# BREADBOARD_MATTRIX.net
KiCad netlist of a schematic drawn in Altium Designer
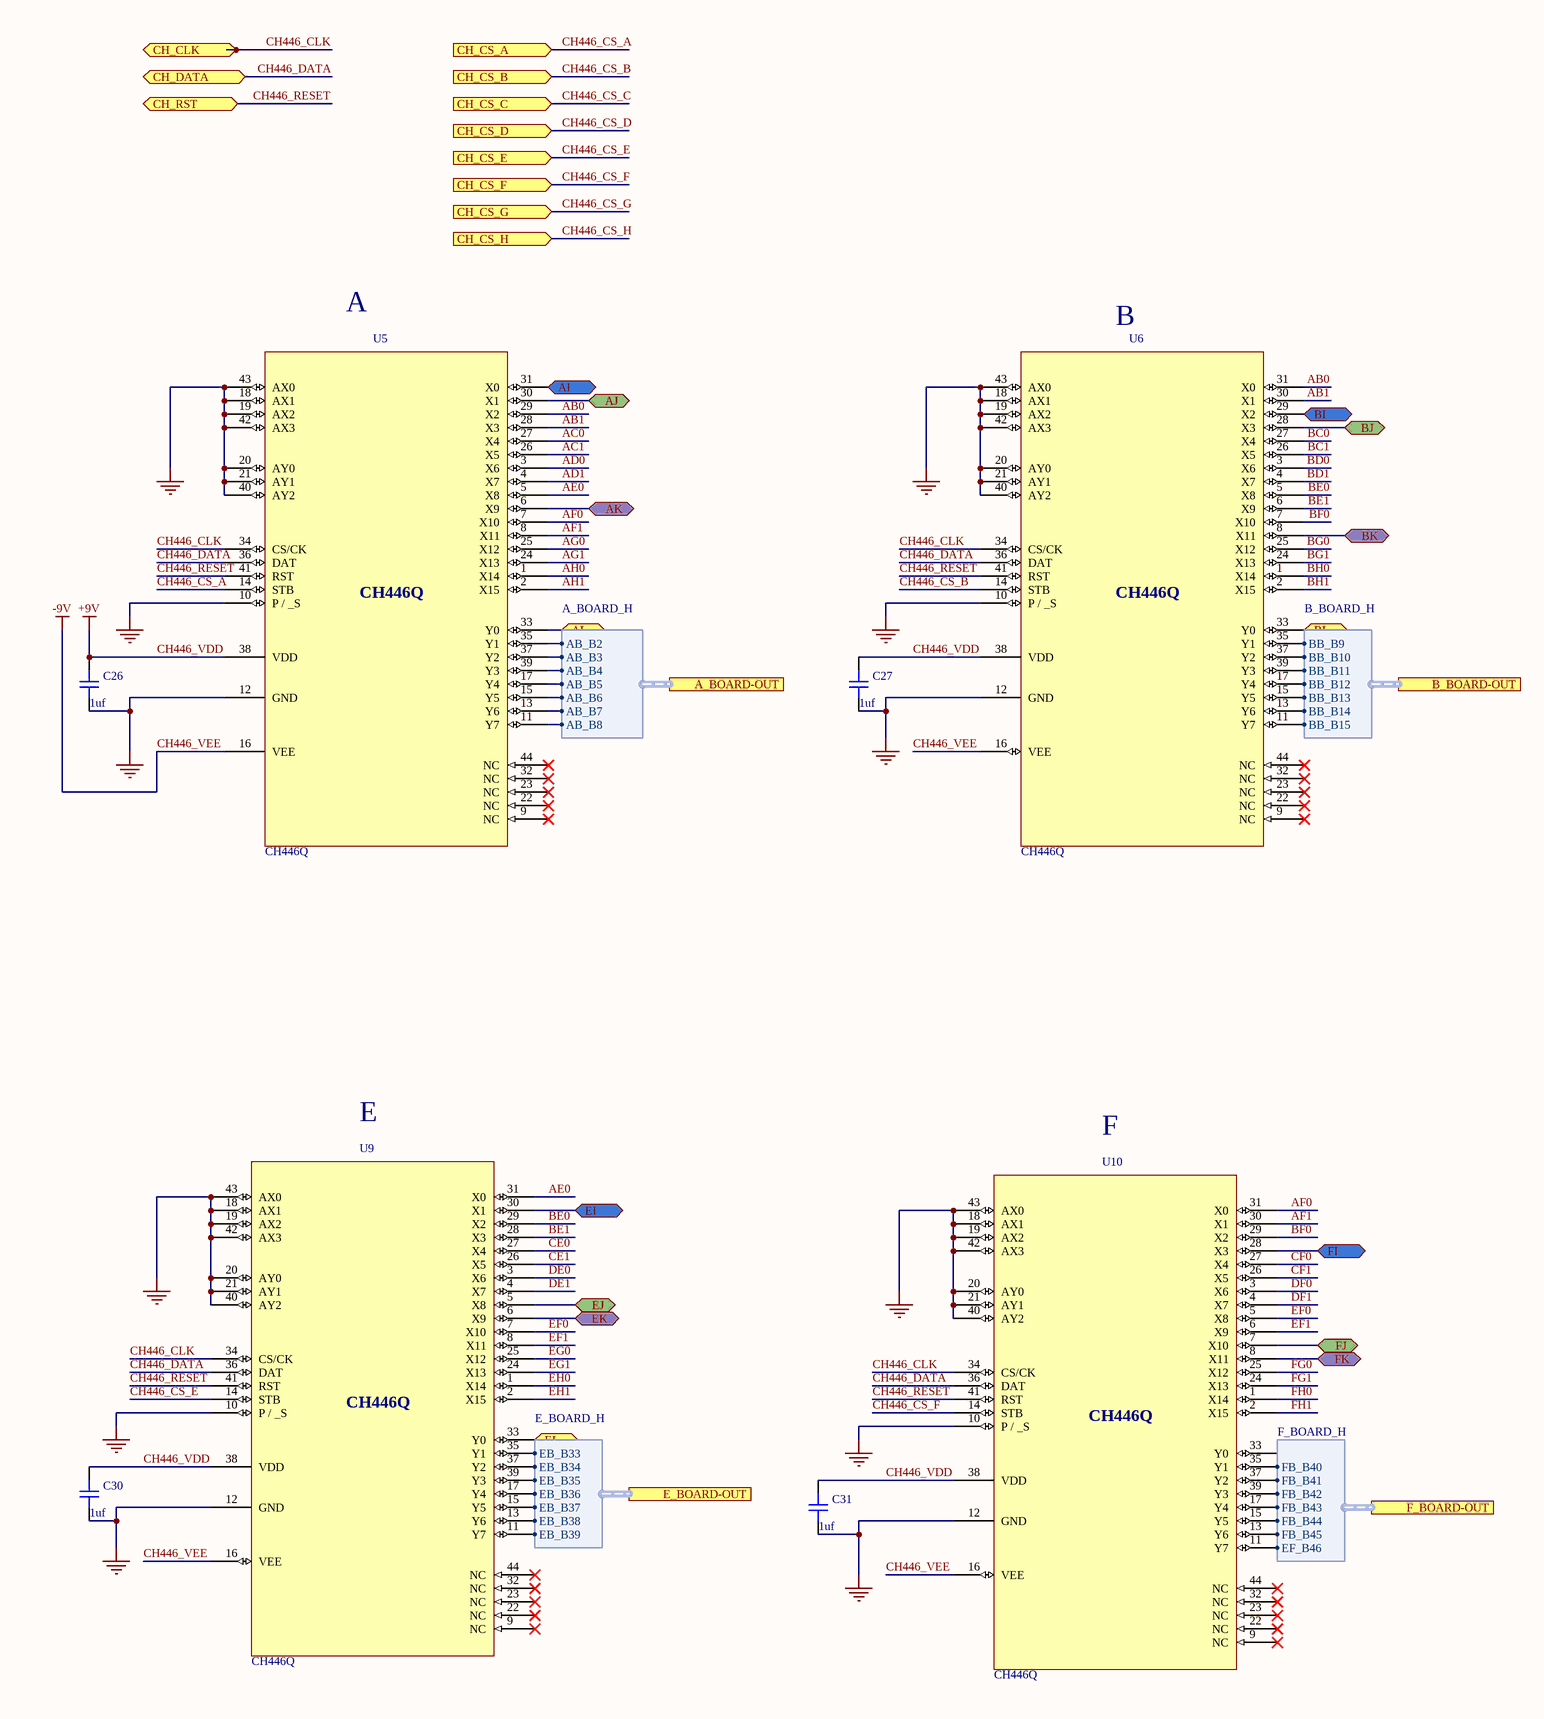
[diagram p0: BREADBOARD_MATTRIX.SchDoc, left]
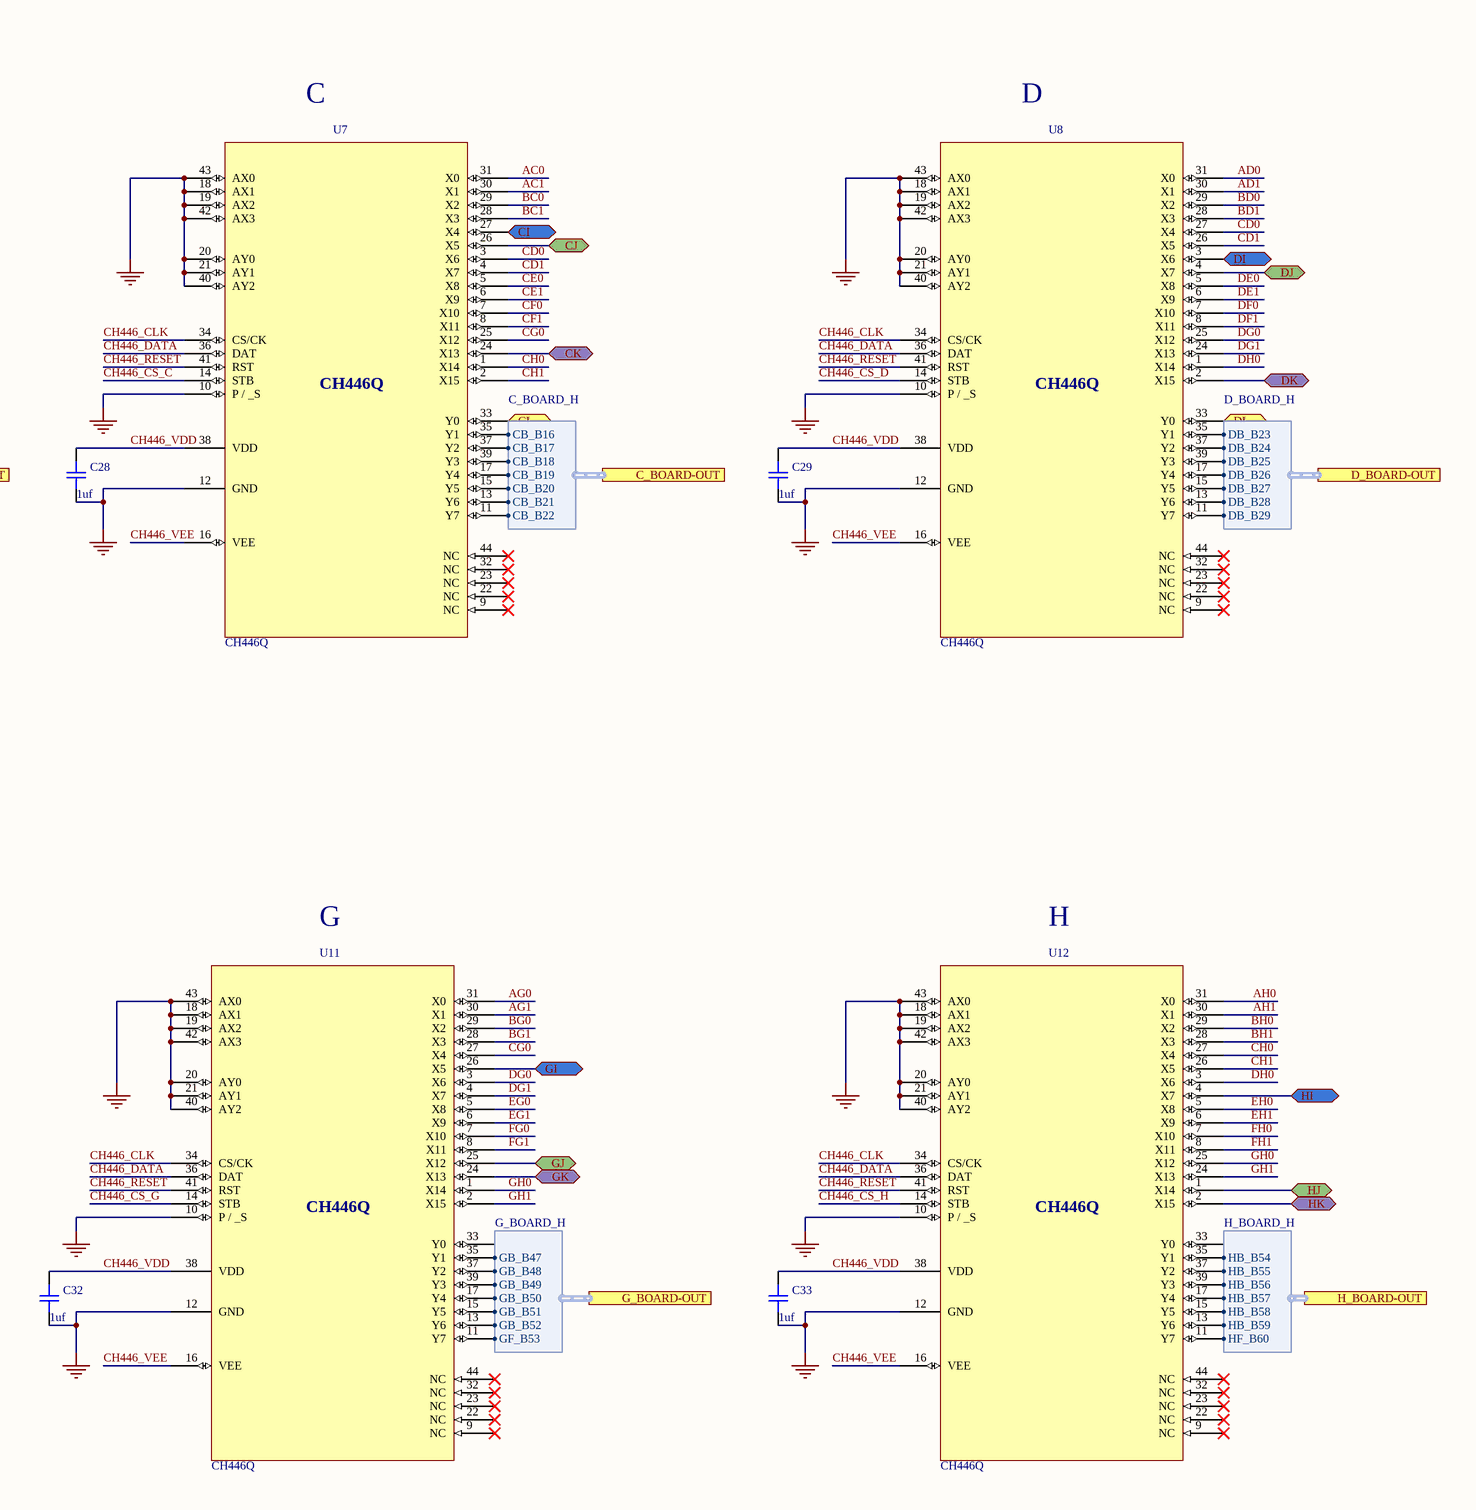
[diagram p1: BREADBOARD_MATTRIX.SchDoc, right]

(export (version "E")
  (design (tool "Eeschema 10.0.6"))
  (components
    (comp (ref "C26")
      (value "1uf")
      (footprint "CAP_0603")
      (description "Capacitor SMD 0603")
      (libsource (lib "Schematic-Lib-PhilsLab") (part "CAP_0603"))
    )
    (comp (ref "C27")
      (value "1uf")
      (footprint "CAP_0603")
      (description "Capacitor SMD 0603")
      (libsource (lib "Schematic-Lib-PhilsLab") (part "CAP_0603"))
    )
    (comp (ref "C28")
      (value "1uf")
      (footprint "CAP_0603")
      (description "Capacitor SMD 0603")
      (libsource (lib "Schematic-Lib-PhilsLab") (part "CAP_0603"))
    )
    (comp (ref "C29")
      (value "1uf")
      (footprint "CAP_0603")
      (description "Capacitor SMD 0603")
      (libsource (lib "Schematic-Lib-PhilsLab") (part "CAP_0603"))
    )
    (comp (ref "C30")
      (value "1uf")
      (footprint "CAP_0603")
      (description "Capacitor SMD 0603")
      (libsource (lib "Schematic-Lib-PhilsLab") (part "CAP_0603"))
    )
    (comp (ref "C31")
      (value "1uf")
      (footprint "CAP_0603")
      (description "Capacitor SMD 0603")
      (libsource (lib "Schematic-Lib-PhilsLab") (part "CAP_0603"))
    )
    (comp (ref "C32")
      (value "1uf")
      (footprint "CAP_0603")
      (description "Capacitor SMD 0603")
      (libsource (lib "Schematic-Lib-PhilsLab") (part "CAP_0603"))
    )
    (comp (ref "C33")
      (value "1uf")
      (footprint "CAP_0603")
      (description "Capacitor SMD 0603")
      (libsource (lib "Schematic-Lib-PhilsLab") (part "CAP_0603"))
    )
    (comp (ref "U5") (value "CH446Q") (footprint "PG-LQFP-44") (libsource (lib "Schlib1") (part "CH446Q")))
    (comp (ref "U6") (value "CH446Q") (footprint "PG-LQFP-44") (libsource (lib "Schlib1") (part "CH446Q")))
    (comp (ref "U7") (value "CH446Q") (footprint "PG-LQFP-44") (libsource (lib "Schlib1") (part "CH446Q")))
    (comp (ref "U8") (value "CH446Q") (footprint "PG-LQFP-44") (libsource (lib "Schlib1") (part "CH446Q")))
    (comp (ref "U9") (value "CH446Q") (footprint "PG-LQFP-44") (libsource (lib "Schlib1") (part "CH446Q")))
    (comp (ref "U10") (value "CH446Q") (footprint "PG-LQFP-44") (libsource (lib "Schlib1") (part "CH446Q")))
    (comp (ref "U11") (value "CH446Q") (footprint "PG-LQFP-44") (libsource (lib "Schlib1") (part "CH446Q")))
    (comp (ref "U12") (value "CH446Q") (footprint "PG-LQFP-44") (libsource (lib "Schlib1") (part "CH446Q")))
  )
  (nets
    (net (code "9") (name "+9V") (class "Default")
      (node (ref "C26") (pin "2") (pinfunction "2_2") (pintype "passive"))
      (node (ref "C27") (pin "2") (pinfunction "2_2") (pintype "passive"))
      (node (ref "C28") (pin "2") (pinfunction "2_2") (pintype "passive"))
      (node (ref "C29") (pin "2") (pinfunction "2_2") (pintype "passive"))
      (node (ref "C30") (pin "2") (pinfunction "2_2") (pintype "passive"))
      (node (ref "C31") (pin "2") (pinfunction "2_2") (pintype "passive"))
      (node (ref "C32") (pin "2") (pinfunction "2_2") (pintype "passive"))
      (node (ref "C33") (pin "2") (pinfunction "2_2") (pintype "passive"))
      (node (ref "U10") (pin "38") (pinfunction "VDD_38") (pintype "power_in"))
      (node (ref "U11") (pin "38") (pinfunction "VDD_38") (pintype "power_in"))
      (node (ref "U12") (pin "38") (pinfunction "VDD_38") (pintype "power_in"))
      (node (ref "U5") (pin "38") (pinfunction "VDD_38") (pintype "power_in"))
      (node (ref "U6") (pin "38") (pinfunction "VDD_38") (pintype "power_in"))
      (node (ref "U7") (pin "38") (pinfunction "VDD_38") (pintype "power_in"))
      (node (ref "U8") (pin "38") (pinfunction "VDD_38") (pintype "power_in"))
      (node (ref "U9") (pin "38") (pinfunction "VDD_38") (pintype "power_in"))
    )
    (net (code "10") (name "-9V") (class "Default")
      (node (ref "U10") (pin "16") (pinfunction "VEE_16") (pintype "bidirectional"))
      (node (ref "U11") (pin "16") (pinfunction "VEE_16") (pintype "bidirectional"))
      (node (ref "U12") (pin "16") (pinfunction "VEE_16") (pintype "bidirectional"))
      (node (ref "U5") (pin "16") (pinfunction "VEE_16") (pintype "bidirectional"))
      (node (ref "U6") (pin "16") (pinfunction "VEE_16") (pintype "bidirectional"))
      (node (ref "U7") (pin "16") (pinfunction "VEE_16") (pintype "bidirectional"))
      (node (ref "U8") (pin "16") (pinfunction "VEE_16") (pintype "bidirectional"))
      (node (ref "U9") (pin "16") (pinfunction "VEE_16") (pintype "bidirectional"))
    )
    (net (code "11") (name "/AB0") (class "Default")
      (node (ref "U5") (pin "29") (pinfunction "X2_29") (pintype "bidirectional"))
      (node (ref "U6") (pin "31") (pinfunction "X0_31") (pintype "bidirectional"))
    )
    (net (code "12") (name "/AB1") (class "Default")
      (node (ref "U5") (pin "28") (pinfunction "X3_28") (pintype "bidirectional"))
      (node (ref "U6") (pin "30") (pinfunction "X1_30") (pintype "bidirectional"))
    )
    (net (code "13") (name "/AB_B2") (class "Default")
      (node (ref "U5") (pin "35") (pinfunction "Y1_35") (pintype "bidirectional"))
    )
    (net (code "14") (name "/AB_B3") (class "Default")
      (node (ref "U5") (pin "37") (pinfunction "Y2_37") (pintype "bidirectional"))
    )
    (net (code "15") (name "/AB_B4") (class "Default")
      (node (ref "U5") (pin "39") (pinfunction "Y3_39") (pintype "bidirectional"))
    )
    (net (code "16") (name "/AB_B5") (class "Default")
      (node (ref "U5") (pin "17") (pinfunction "Y4_17") (pintype "bidirectional"))
    )
    (net (code "17") (name "/AB_B6") (class "Default")
      (node (ref "U5") (pin "15") (pinfunction "Y5_15") (pintype "bidirectional"))
    )
    (net (code "18") (name "/AB_B7") (class "Default")
      (node (ref "U5") (pin "13") (pinfunction "Y6_13") (pintype "bidirectional"))
    )
    (net (code "19") (name "/AB_B8") (class "Default")
      (node (ref "U5") (pin "11") (pinfunction "Y7_11") (pintype "bidirectional"))
    )
    (net (code "20") (name "/AC0") (class "Default")
      (node (ref "U5") (pin "27") (pinfunction "X4_27") (pintype "bidirectional"))
      (node (ref "U7") (pin "31") (pinfunction "X0_31") (pintype "bidirectional"))
    )
    (net (code "21") (name "/AC1") (class "Default")
      (node (ref "U5") (pin "26") (pinfunction "X5_26") (pintype "bidirectional"))
      (node (ref "U7") (pin "30") (pinfunction "X1_30") (pintype "bidirectional"))
    )
    (net (code "22") (name "/AD0") (class "Default")
      (node (ref "U5") (pin "3") (pinfunction "X6_3") (pintype "bidirectional"))
      (node (ref "U8") (pin "31") (pinfunction "X0_31") (pintype "bidirectional"))
    )
    (net (code "23") (name "/AD1") (class "Default")
      (node (ref "U5") (pin "4") (pinfunction "X7_4") (pintype "bidirectional"))
      (node (ref "U8") (pin "30") (pinfunction "X1_30") (pintype "bidirectional"))
    )
    (net (code "24") (name "/AE0") (class "Default")
      (node (ref "U5") (pin "5") (pinfunction "X8_5") (pintype "bidirectional"))
      (node (ref "U9") (pin "31") (pinfunction "X0_31") (pintype "bidirectional"))
    )
    (net (code "25") (name "/AF0") (class "Default")
      (node (ref "U10") (pin "31") (pinfunction "X0_31") (pintype "bidirectional"))
      (node (ref "U5") (pin "7") (pinfunction "X10_7") (pintype "bidirectional"))
    )
    (net (code "26") (name "/AF1") (class "Default")
      (node (ref "U10") (pin "30") (pinfunction "X1_30") (pintype "bidirectional"))
      (node (ref "U5") (pin "8") (pinfunction "X11_8") (pintype "bidirectional"))
    )
    (net (code "27") (name "/AG0") (class "Default")
      (node (ref "U11") (pin "31") (pinfunction "X0_31") (pintype "bidirectional"))
      (node (ref "U5") (pin "25") (pinfunction "X12_25") (pintype "bidirectional"))
    )
    (net (code "28") (name "/AG1") (class "Default")
      (node (ref "U11") (pin "30") (pinfunction "X1_30") (pintype "bidirectional"))
      (node (ref "U5") (pin "24") (pinfunction "X13_24") (pintype "bidirectional"))
    )
    (net (code "29") (name "/AH0") (class "Default")
      (node (ref "U12") (pin "31") (pinfunction "X0_31") (pintype "bidirectional"))
      (node (ref "U5") (pin "1") (pinfunction "X14_1") (pintype "bidirectional"))
    )
    (net (code "30") (name "/AH1") (class "Default")
      (node (ref "U12") (pin "30") (pinfunction "X1_30") (pintype "bidirectional"))
      (node (ref "U5") (pin "2") (pinfunction "X15_2") (pintype "bidirectional"))
    )
    (net (code "31") (name "/AI") (class "Default")
      (node (ref "U5") (pin "31") (pinfunction "X0_31") (pintype "bidirectional"))
    )
    (net (code "32") (name "/AJ") (class "Default")
      (node (ref "U5") (pin "30") (pinfunction "X1_30") (pintype "bidirectional"))
    )
    (net (code "33") (name "/AK") (class "Default")
      (node (ref "U5") (pin "6") (pinfunction "X9_6") (pintype "bidirectional"))
    )
    (net (code "34") (name "/AL") (class "Default")
      (node (ref "U5") (pin "33") (pinfunction "Y0_33") (pintype "bidirectional"))
    )
    (net (code "35") (name "/BB_B9") (class "Default")
      (node (ref "U6") (pin "35") (pinfunction "Y1_35") (pintype "bidirectional"))
    )
    (net (code "36") (name "/BB_B10") (class "Default")
      (node (ref "U6") (pin "37") (pinfunction "Y2_37") (pintype "bidirectional"))
    )
    (net (code "37") (name "/BB_B11") (class "Default")
      (node (ref "U6") (pin "39") (pinfunction "Y3_39") (pintype "bidirectional"))
    )
    (net (code "38") (name "/BB_B12") (class "Default")
      (node (ref "U6") (pin "17") (pinfunction "Y4_17") (pintype "bidirectional"))
    )
    (net (code "39") (name "/BB_B13") (class "Default")
      (node (ref "U6") (pin "15") (pinfunction "Y5_15") (pintype "bidirectional"))
    )
    (net (code "40") (name "/BB_B14") (class "Default")
      (node (ref "U6") (pin "13") (pinfunction "Y6_13") (pintype "bidirectional"))
    )
    (net (code "41") (name "/BB_B15") (class "Default")
      (node (ref "U6") (pin "11") (pinfunction "Y7_11") (pintype "bidirectional"))
    )
    (net (code "42") (name "/BC0") (class "Default")
      (node (ref "U6") (pin "27") (pinfunction "X4_27") (pintype "bidirectional"))
      (node (ref "U7") (pin "29") (pinfunction "X2_29") (pintype "bidirectional"))
    )
    (net (code "43") (name "/BC1") (class "Default")
      (node (ref "U6") (pin "26") (pinfunction "X5_26") (pintype "bidirectional"))
      (node (ref "U7") (pin "28") (pinfunction "X3_28") (pintype "bidirectional"))
    )
    (net (code "44") (name "/BD0") (class "Default")
      (node (ref "U6") (pin "3") (pinfunction "X6_3") (pintype "bidirectional"))
      (node (ref "U8") (pin "29") (pinfunction "X2_29") (pintype "bidirectional"))
    )
    (net (code "45") (name "/BD1") (class "Default")
      (node (ref "U6") (pin "4") (pinfunction "X7_4") (pintype "bidirectional"))
      (node (ref "U8") (pin "28") (pinfunction "X3_28") (pintype "bidirectional"))
    )
    (net (code "46") (name "/BE0") (class "Default")
      (node (ref "U6") (pin "5") (pinfunction "X8_5") (pintype "bidirectional"))
      (node (ref "U9") (pin "29") (pinfunction "X2_29") (pintype "bidirectional"))
    )
    (net (code "47") (name "/BE1") (class "Default")
      (node (ref "U6") (pin "6") (pinfunction "X9_6") (pintype "bidirectional"))
      (node (ref "U9") (pin "28") (pinfunction "X3_28") (pintype "bidirectional"))
    )
    (net (code "48") (name "/BF0") (class "Default")
      (node (ref "U10") (pin "29") (pinfunction "X2_29") (pintype "bidirectional"))
      (node (ref "U6") (pin "7") (pinfunction "X10_7") (pintype "bidirectional"))
    )
    (net (code "49") (name "/BG0") (class "Default")
      (node (ref "U11") (pin "29") (pinfunction "X2_29") (pintype "bidirectional"))
      (node (ref "U6") (pin "25") (pinfunction "X12_25") (pintype "bidirectional"))
    )
    (net (code "50") (name "/BG1") (class "Default")
      (node (ref "U11") (pin "28") (pinfunction "X3_28") (pintype "bidirectional"))
      (node (ref "U6") (pin "24") (pinfunction "X13_24") (pintype "bidirectional"))
    )
    (net (code "51") (name "/BH0") (class "Default")
      (node (ref "U12") (pin "29") (pinfunction "X2_29") (pintype "bidirectional"))
      (node (ref "U6") (pin "1") (pinfunction "X14_1") (pintype "bidirectional"))
    )
    (net (code "52") (name "/BH1") (class "Default")
      (node (ref "U12") (pin "28") (pinfunction "X3_28") (pintype "bidirectional"))
      (node (ref "U6") (pin "2") (pinfunction "X15_2") (pintype "bidirectional"))
    )
    (net (code "53") (name "/BI") (class "Default")
      (node (ref "U6") (pin "29") (pinfunction "X2_29") (pintype "bidirectional"))
    )
    (net (code "54") (name "/BJ") (class "Default")
      (node (ref "U6") (pin "28") (pinfunction "X3_28") (pintype "bidirectional"))
    )
    (net (code "55") (name "/BK") (class "Default")
      (node (ref "U6") (pin "8") (pinfunction "X11_8") (pintype "bidirectional"))
    )
    (net (code "56") (name "/BL") (class "Default")
      (node (ref "U6") (pin "33") (pinfunction "Y0_33") (pintype "bidirectional"))
    )
    (net (code "57") (name "/CB_B16") (class "Default")
      (node (ref "U7") (pin "35") (pinfunction "Y1_35") (pintype "bidirectional"))
    )
    (net (code "58") (name "/CB_B17") (class "Default")
      (node (ref "U7") (pin "37") (pinfunction "Y2_37") (pintype "bidirectional"))
    )
    (net (code "59") (name "/CB_B18") (class "Default")
      (node (ref "U7") (pin "39") (pinfunction "Y3_39") (pintype "bidirectional"))
    )
    (net (code "60") (name "/CB_B19") (class "Default")
      (node (ref "U7") (pin "17") (pinfunction "Y4_17") (pintype "bidirectional"))
    )
    (net (code "61") (name "/CB_B20") (class "Default")
      (node (ref "U7") (pin "15") (pinfunction "Y5_15") (pintype "bidirectional"))
    )
    (net (code "62") (name "/CB_B21") (class "Default")
      (node (ref "U7") (pin "13") (pinfunction "Y6_13") (pintype "bidirectional"))
    )
    (net (code "63") (name "/CB_B22") (class "Default")
      (node (ref "U7") (pin "11") (pinfunction "Y7_11") (pintype "bidirectional"))
    )
    (net (code "64") (name "/CD0") (class "Default")
      (node (ref "U7") (pin "3") (pinfunction "X6_3") (pintype "bidirectional"))
      (node (ref "U8") (pin "27") (pinfunction "X4_27") (pintype "bidirectional"))
    )
    (net (code "65") (name "/CD1") (class "Default")
      (node (ref "U7") (pin "4") (pinfunction "X7_4") (pintype "bidirectional"))
      (node (ref "U8") (pin "26") (pinfunction "X5_26") (pintype "bidirectional"))
    )
    (net (code "66") (name "/CE0") (class "Default")
      (node (ref "U7") (pin "5") (pinfunction "X8_5") (pintype "bidirectional"))
      (node (ref "U9") (pin "27") (pinfunction "X4_27") (pintype "bidirectional"))
    )
    (net (code "67") (name "/CE1") (class "Default")
      (node (ref "U7") (pin "6") (pinfunction "X9_6") (pintype "bidirectional"))
      (node (ref "U9") (pin "26") (pinfunction "X5_26") (pintype "bidirectional"))
    )
    (net (code "68") (name "/CF0") (class "Default")
      (node (ref "U10") (pin "27") (pinfunction "X4_27") (pintype "bidirectional"))
      (node (ref "U7") (pin "7") (pinfunction "X10_7") (pintype "bidirectional"))
    )
    (net (code "69") (name "/CF1") (class "Default")
      (node (ref "U10") (pin "26") (pinfunction "X5_26") (pintype "bidirectional"))
      (node (ref "U7") (pin "8") (pinfunction "X11_8") (pintype "bidirectional"))
    )
    (net (code "70") (name "/CG0") (class "Default")
      (node (ref "U11") (pin "27") (pinfunction "X4_27") (pintype "bidirectional"))
      (node (ref "U7") (pin "25") (pinfunction "X12_25") (pintype "bidirectional"))
    )
    (net (code "71") (name "/CH0") (class "Default")
      (node (ref "U12") (pin "27") (pinfunction "X4_27") (pintype "bidirectional"))
      (node (ref "U7") (pin "1") (pinfunction "X14_1") (pintype "bidirectional"))
    )
    (net (code "72") (name "/CH1") (class "Default")
      (node (ref "U12") (pin "26") (pinfunction "X5_26") (pintype "bidirectional"))
      (node (ref "U7") (pin "2") (pinfunction "X15_2") (pintype "bidirectional"))
    )
    (net (code "73") (name "/CH446_CLK") (class "Default")
      (node (ref "U10") (pin "34") (pinfunction "CS/CK_34") (pintype "bidirectional"))
      (node (ref "U11") (pin "34") (pinfunction "CS/CK_34") (pintype "bidirectional"))
      (node (ref "U12") (pin "34") (pinfunction "CS/CK_34") (pintype "bidirectional"))
      (node (ref "U5") (pin "34") (pinfunction "CS/CK_34") (pintype "bidirectional"))
      (node (ref "U6") (pin "34") (pinfunction "CS/CK_34") (pintype "bidirectional"))
      (node (ref "U7") (pin "34") (pinfunction "CS/CK_34") (pintype "bidirectional"))
      (node (ref "U8") (pin "34") (pinfunction "CS/CK_34") (pintype "bidirectional"))
      (node (ref "U9") (pin "34") (pinfunction "CS/CK_34") (pintype "bidirectional"))
    )
    (net (code "74") (name "/CH446_CS_A") (class "Default")
      (node (ref "U5") (pin "14") (pinfunction "STB_14") (pintype "bidirectional"))
    )
    (net (code "75") (name "/CH446_CS_B") (class "Default")
      (node (ref "U6") (pin "14") (pinfunction "STB_14") (pintype "bidirectional"))
    )
    (net (code "76") (name "/CH446_CS_C") (class "Default")
      (node (ref "U7") (pin "14") (pinfunction "STB_14") (pintype "bidirectional"))
    )
    (net (code "77") (name "/CH446_CS_D") (class "Default")
      (node (ref "U8") (pin "14") (pinfunction "STB_14") (pintype "bidirectional"))
    )
    (net (code "78") (name "/CH446_CS_E") (class "Default")
      (node (ref "U9") (pin "14") (pinfunction "STB_14") (pintype "bidirectional"))
    )
    (net (code "79") (name "/CH446_CS_F") (class "Default")
      (node (ref "U10") (pin "14") (pinfunction "STB_14") (pintype "bidirectional"))
    )
    (net (code "80") (name "/CH446_CS_G") (class "Default")
      (node (ref "U11") (pin "14") (pinfunction "STB_14") (pintype "bidirectional"))
    )
    (net (code "81") (name "/CH446_CS_H") (class "Default")
      (node (ref "U12") (pin "14") (pinfunction "STB_14") (pintype "bidirectional"))
    )
    (net (code "82") (name "/CH446_DATA") (class "Default")
      (node (ref "U10") (pin "36") (pinfunction "DAT_36") (pintype "bidirectional"))
      (node (ref "U11") (pin "36") (pinfunction "DAT_36") (pintype "bidirectional"))
      (node (ref "U12") (pin "36") (pinfunction "DAT_36") (pintype "bidirectional"))
      (node (ref "U5") (pin "36") (pinfunction "DAT_36") (pintype "bidirectional"))
      (node (ref "U6") (pin "36") (pinfunction "DAT_36") (pintype "bidirectional"))
      (node (ref "U7") (pin "36") (pinfunction "DAT_36") (pintype "bidirectional"))
      (node (ref "U8") (pin "36") (pinfunction "DAT_36") (pintype "bidirectional"))
      (node (ref "U9") (pin "36") (pinfunction "DAT_36") (pintype "bidirectional"))
    )
    (net (code "83") (name "/CH446_RESET") (class "Default")
      (node (ref "U10") (pin "41") (pinfunction "RST_41") (pintype "bidirectional"))
      (node (ref "U11") (pin "41") (pinfunction "RST_41") (pintype "bidirectional"))
      (node (ref "U12") (pin "41") (pinfunction "RST_41") (pintype "bidirectional"))
      (node (ref "U5") (pin "41") (pinfunction "RST_41") (pintype "bidirectional"))
      (node (ref "U6") (pin "41") (pinfunction "RST_41") (pintype "bidirectional"))
      (node (ref "U7") (pin "41") (pinfunction "RST_41") (pintype "bidirectional"))
      (node (ref "U8") (pin "41") (pinfunction "RST_41") (pintype "bidirectional"))
      (node (ref "U9") (pin "41") (pinfunction "RST_41") (pintype "bidirectional"))
    )
    (net (code "84") (name "/CI") (class "Default")
      (node (ref "U7") (pin "27") (pinfunction "X4_27") (pintype "bidirectional"))
    )
    (net (code "85") (name "/CJ") (class "Default")
      (node (ref "U7") (pin "26") (pinfunction "X5_26") (pintype "bidirectional"))
    )
    (net (code "86") (name "/CK") (class "Default")
      (node (ref "U7") (pin "24") (pinfunction "X13_24") (pintype "bidirectional"))
    )
    (net (code "87") (name "/CL") (class "Default")
      (node (ref "U7") (pin "33") (pinfunction "Y0_33") (pintype "bidirectional"))
    )
    (net (code "88") (name "/DB_B23") (class "Default")
      (node (ref "U8") (pin "35") (pinfunction "Y1_35") (pintype "bidirectional"))
    )
    (net (code "89") (name "/DB_B24") (class "Default")
      (node (ref "U8") (pin "37") (pinfunction "Y2_37") (pintype "bidirectional"))
    )
    (net (code "90") (name "/DB_B25") (class "Default")
      (node (ref "U8") (pin "39") (pinfunction "Y3_39") (pintype "bidirectional"))
    )
    (net (code "91") (name "/DB_B26") (class "Default")
      (node (ref "U8") (pin "17") (pinfunction "Y4_17") (pintype "bidirectional"))
    )
    (net (code "92") (name "/DB_B27") (class "Default")
      (node (ref "U8") (pin "15") (pinfunction "Y5_15") (pintype "bidirectional"))
    )
    (net (code "93") (name "/DB_B28") (class "Default")
      (node (ref "U8") (pin "13") (pinfunction "Y6_13") (pintype "bidirectional"))
    )
    (net (code "94") (name "/DB_B29") (class "Default")
      (node (ref "U8") (pin "11") (pinfunction "Y7_11") (pintype "bidirectional"))
    )
    (net (code "95") (name "/DE0") (class "Default")
      (node (ref "U8") (pin "5") (pinfunction "X8_5") (pintype "bidirectional"))
      (node (ref "U9") (pin "3") (pinfunction "X6_3") (pintype "bidirectional"))
    )
    (net (code "96") (name "/DE1") (class "Default")
      (node (ref "U8") (pin "6") (pinfunction "X9_6") (pintype "bidirectional"))
      (node (ref "U9") (pin "4") (pinfunction "X7_4") (pintype "bidirectional"))
    )
    (net (code "97") (name "/DF0") (class "Default")
      (node (ref "U10") (pin "3") (pinfunction "X6_3") (pintype "bidirectional"))
      (node (ref "U8") (pin "7") (pinfunction "X10_7") (pintype "bidirectional"))
    )
    (net (code "98") (name "/DF1") (class "Default")
      (node (ref "U10") (pin "4") (pinfunction "X7_4") (pintype "bidirectional"))
      (node (ref "U8") (pin "8") (pinfunction "X11_8") (pintype "bidirectional"))
    )
    (net (code "99") (name "/DG0") (class "Default")
      (node (ref "U11") (pin "3") (pinfunction "X6_3") (pintype "bidirectional"))
      (node (ref "U8") (pin "25") (pinfunction "X12_25") (pintype "bidirectional"))
    )
    (net (code "100") (name "/DG1") (class "Default")
      (node (ref "U11") (pin "4") (pinfunction "X7_4") (pintype "bidirectional"))
      (node (ref "U8") (pin "24") (pinfunction "X13_24") (pintype "bidirectional"))
    )
    (net (code "101") (name "/DH0") (class "Default")
      (node (ref "U12") (pin "3") (pinfunction "X6_3") (pintype "bidirectional"))
      (node (ref "U8") (pin "1") (pinfunction "X14_1") (pintype "bidirectional"))
    )
    (net (code "102") (name "/DI") (class "Default")
      (node (ref "U8") (pin "3") (pinfunction "X6_3") (pintype "bidirectional"))
    )
    (net (code "103") (name "/DJ") (class "Default")
      (node (ref "U8") (pin "4") (pinfunction "X7_4") (pintype "bidirectional"))
    )
    (net (code "104") (name "/DK") (class "Default")
      (node (ref "U8") (pin "2") (pinfunction "X15_2") (pintype "bidirectional"))
    )
    (net (code "105") (name "/DL") (class "Default")
      (node (ref "U8") (pin "33") (pinfunction "Y0_33") (pintype "bidirectional"))
    )
    (net (code "106") (name "/EB_B33") (class "Default")
      (node (ref "U9") (pin "35") (pinfunction "Y1_35") (pintype "bidirectional"))
    )
    (net (code "107") (name "/EB_B34") (class "Default")
      (node (ref "U9") (pin "37") (pinfunction "Y2_37") (pintype "bidirectional"))
    )
    (net (code "108") (name "/EB_B35") (class "Default")
      (node (ref "U9") (pin "39") (pinfunction "Y3_39") (pintype "bidirectional"))
    )
    (net (code "109") (name "/EB_B36") (class "Default")
      (node (ref "U9") (pin "17") (pinfunction "Y4_17") (pintype "bidirectional"))
    )
    (net (code "110") (name "/EB_B37") (class "Default")
      (node (ref "U9") (pin "15") (pinfunction "Y5_15") (pintype "bidirectional"))
    )
    (net (code "111") (name "/EB_B38") (class "Default")
      (node (ref "U9") (pin "13") (pinfunction "Y6_13") (pintype "bidirectional"))
    )
    (net (code "112") (name "/EB_B39") (class "Default")
      (node (ref "U9") (pin "11") (pinfunction "Y7_11") (pintype "bidirectional"))
    )
    (net (code "113") (name "/EF0") (class "Default")
      (node (ref "U10") (pin "5") (pinfunction "X8_5") (pintype "bidirectional"))
      (node (ref "U9") (pin "7") (pinfunction "X10_7") (pintype "bidirectional"))
    )
    (net (code "114") (name "/EF1") (class "Default")
      (node (ref "U10") (pin "6") (pinfunction "X9_6") (pintype "bidirectional"))
      (node (ref "U9") (pin "8") (pinfunction "X11_8") (pintype "bidirectional"))
    )
    (net (code "115") (name "/EF_B46") (class "Default")
      (node (ref "U10") (pin "11") (pinfunction "Y7_11") (pintype "bidirectional"))
    )
    (net (code "116") (name "/EG0") (class "Default")
      (node (ref "U11") (pin "5") (pinfunction "X8_5") (pintype "bidirectional"))
      (node (ref "U9") (pin "25") (pinfunction "X12_25") (pintype "bidirectional"))
    )
    (net (code "117") (name "/EG1") (class "Default")
      (node (ref "U11") (pin "6") (pinfunction "X9_6") (pintype "bidirectional"))
      (node (ref "U9") (pin "24") (pinfunction "X13_24") (pintype "bidirectional"))
    )
    (net (code "118") (name "/EH0") (class "Default")
      (node (ref "U12") (pin "5") (pinfunction "X8_5") (pintype "bidirectional"))
      (node (ref "U9") (pin "1") (pinfunction "X14_1") (pintype "bidirectional"))
    )
    (net (code "119") (name "/EH1") (class "Default")
      (node (ref "U12") (pin "6") (pinfunction "X9_6") (pintype "bidirectional"))
      (node (ref "U9") (pin "2") (pinfunction "X15_2") (pintype "bidirectional"))
    )
    (net (code "120") (name "/EI") (class "Default")
      (node (ref "U9") (pin "30") (pinfunction "X1_30") (pintype "bidirectional"))
    )
    (net (code "121") (name "/EJ") (class "Default")
      (node (ref "U9") (pin "5") (pinfunction "X8_5") (pintype "bidirectional"))
    )
    (net (code "122") (name "/EK") (class "Default")
      (node (ref "U9") (pin "6") (pinfunction "X9_6") (pintype "bidirectional"))
    )
    (net (code "123") (name "/EL") (class "Default")
      (node (ref "U9") (pin "33") (pinfunction "Y0_33") (pintype "bidirectional"))
    )
    (net (code "124") (name "/FB_B40") (class "Default")
      (node (ref "U10") (pin "35") (pinfunction "Y1_35") (pintype "bidirectional"))
    )
    (net (code "125") (name "/FB_B41") (class "Default")
      (node (ref "U10") (pin "37") (pinfunction "Y2_37") (pintype "bidirectional"))
    )
    (net (code "126") (name "/FB_B42") (class "Default")
      (node (ref "U10") (pin "39") (pinfunction "Y3_39") (pintype "bidirectional"))
    )
    (net (code "127") (name "/FB_B43") (class "Default")
      (node (ref "U10") (pin "17") (pinfunction "Y4_17") (pintype "bidirectional"))
    )
    (net (code "128") (name "/FB_B44") (class "Default")
      (node (ref "U10") (pin "15") (pinfunction "Y5_15") (pintype "bidirectional"))
    )
    (net (code "129") (name "/FB_B45") (class "Default")
      (node (ref "U10") (pin "13") (pinfunction "Y6_13") (pintype "bidirectional"))
    )
    (net (code "130") (name "/FG0") (class "Default")
      (node (ref "U10") (pin "25") (pinfunction "X12_25") (pintype "bidirectional"))
      (node (ref "U11") (pin "7") (pinfunction "X10_7") (pintype "bidirectional"))
    )
    (net (code "131") (name "/FG1") (class "Default")
      (node (ref "U10") (pin "24") (pinfunction "X13_24") (pintype "bidirectional"))
      (node (ref "U11") (pin "8") (pinfunction "X11_8") (pintype "bidirectional"))
    )
    (net (code "132") (name "/FH0") (class "Default")
      (node (ref "U10") (pin "1") (pinfunction "X14_1") (pintype "bidirectional"))
      (node (ref "U12") (pin "7") (pinfunction "X10_7") (pintype "bidirectional"))
    )
    (net (code "133") (name "/FH1") (class "Default")
      (node (ref "U10") (pin "2") (pinfunction "X15_2") (pintype "bidirectional"))
      (node (ref "U12") (pin "8") (pinfunction "X11_8") (pintype "bidirectional"))
    )
    (net (code "134") (name "/FI") (class "Default")
      (node (ref "U10") (pin "28") (pinfunction "X3_28") (pintype "bidirectional"))
    )
    (net (code "135") (name "/FJ") (class "Default")
      (node (ref "U10") (pin "7") (pinfunction "X10_7") (pintype "bidirectional"))
    )
    (net (code "136") (name "/FK") (class "Default")
      (node (ref "U10") (pin "8") (pinfunction "X11_8") (pintype "bidirectional"))
    )
    (net (code "137") (name "/FL") (class "Default")
      (node (ref "U10") (pin "33") (pinfunction "Y0_33") (pintype "bidirectional"))
    )
    (net (code "138") (name "/GB_B47") (class "Default")
      (node (ref "U11") (pin "35") (pinfunction "Y1_35") (pintype "bidirectional"))
    )
    (net (code "139") (name "/GB_B48") (class "Default")
      (node (ref "U11") (pin "37") (pinfunction "Y2_37") (pintype "bidirectional"))
    )
    (net (code "140") (name "/GB_B49") (class "Default")
      (node (ref "U11") (pin "39") (pinfunction "Y3_39") (pintype "bidirectional"))
    )
    (net (code "141") (name "/GB_B50") (class "Default")
      (node (ref "U11") (pin "17") (pinfunction "Y4_17") (pintype "bidirectional"))
    )
    (net (code "142") (name "/GB_B51") (class "Default")
      (node (ref "U11") (pin "15") (pinfunction "Y5_15") (pintype "bidirectional"))
    )
    (net (code "143") (name "/GB_B52") (class "Default")
      (node (ref "U11") (pin "13") (pinfunction "Y6_13") (pintype "bidirectional"))
    )
    (net (code "144") (name "/GF_B53") (class "Default")
      (node (ref "U11") (pin "11") (pinfunction "Y7_11") (pintype "bidirectional"))
    )
    (net (code "145") (name "/GH0") (class "Default")
      (node (ref "U11") (pin "1") (pinfunction "X14_1") (pintype "bidirectional"))
      (node (ref "U12") (pin "25") (pinfunction "X12_25") (pintype "bidirectional"))
    )
    (net (code "146") (name "/GH1") (class "Default")
      (node (ref "U11") (pin "2") (pinfunction "X15_2") (pintype "bidirectional"))
      (node (ref "U12") (pin "24") (pinfunction "X13_24") (pintype "bidirectional"))
    )
    (net (code "147") (name "/GI") (class "Default")
      (node (ref "U11") (pin "26") (pinfunction "X5_26") (pintype "bidirectional"))
    )
    (net (code "148") (name "/GJ") (class "Default")
      (node (ref "U11") (pin "25") (pinfunction "X12_25") (pintype "bidirectional"))
    )
    (net (code "149") (name "/GK") (class "Default")
      (node (ref "U11") (pin "24") (pinfunction "X13_24") (pintype "bidirectional"))
    )
    (net (code "150") (name "/GL") (class "Default")
      (node (ref "U11") (pin "33") (pinfunction "Y0_33") (pintype "bidirectional"))
    )
    (net (code "151") (name "/HB_B54") (class "Default")
      (node (ref "U12") (pin "35") (pinfunction "Y1_35") (pintype "bidirectional"))
    )
    (net (code "152") (name "/HB_B55") (class "Default")
      (node (ref "U12") (pin "37") (pinfunction "Y2_37") (pintype "bidirectional"))
    )
    (net (code "153") (name "/HB_B56") (class "Default")
      (node (ref "U12") (pin "39") (pinfunction "Y3_39") (pintype "bidirectional"))
    )
    (net (code "154") (name "/HB_B57") (class "Default")
      (node (ref "U12") (pin "17") (pinfunction "Y4_17") (pintype "bidirectional"))
    )
    (net (code "155") (name "/HB_B58") (class "Default")
      (node (ref "U12") (pin "15") (pinfunction "Y5_15") (pintype "bidirectional"))
    )
    (net (code "156") (name "/HB_B59") (class "Default")
      (node (ref "U12") (pin "13") (pinfunction "Y6_13") (pintype "bidirectional"))
    )
    (net (code "157") (name "/HF_B60") (class "Default")
      (node (ref "U12") (pin "11") (pinfunction "Y7_11") (pintype "bidirectional"))
    )
    (net (code "158") (name "/HI") (class "Default")
      (node (ref "U12") (pin "4") (pinfunction "X7_4") (pintype "bidirectional"))
    )
    (net (code "159") (name "/HJ") (class "Default")
      (node (ref "U12") (pin "1") (pinfunction "X14_1") (pintype "bidirectional"))
    )
    (net (code "160") (name "/HK") (class "Default")
      (node (ref "U12") (pin "2") (pinfunction "X15_2") (pintype "bidirectional"))
    )
    (net (code "161") (name "/HL") (class "Default")
      (node (ref "U12") (pin "33") (pinfunction "Y0_33") (pintype "bidirectional"))
    )
    (net (code "170") (name "GND") (class "Default")
      (node (ref "C26") (pin "1") (pinfunction "1_1") (pintype "passive"))
      (node (ref "C27") (pin "1") (pinfunction "1_1") (pintype "passive"))
      (node (ref "C28") (pin "1") (pinfunction "1_1") (pintype "passive"))
      (node (ref "C29") (pin "1") (pinfunction "1_1") (pintype "passive"))
      (node (ref "C30") (pin "1") (pinfunction "1_1") (pintype "passive"))
      (node (ref "C31") (pin "1") (pinfunction "1_1") (pintype "passive"))
      (node (ref "C32") (pin "1") (pinfunction "1_1") (pintype "passive"))
      (node (ref "C33") (pin "1") (pinfunction "1_1") (pintype "passive"))
      (node (ref "U10") (pin "10") (pinfunction "P_/__S_10") (pintype "bidirectional"))
      (node (ref "U10") (pin "12") (pinfunction "GND_12") (pintype "power_in"))
      (node (ref "U10") (pin "18") (pinfunction "AX1_18") (pintype "bidirectional"))
      (node (ref "U10") (pin "19") (pinfunction "AX2_19") (pintype "bidirectional"))
      (node (ref "U10") (pin "20") (pinfunction "AY0_20") (pintype "bidirectional"))
      (node (ref "U10") (pin "21") (pinfunction "AY1_21") (pintype "bidirectional"))
      (node (ref "U10") (pin "40") (pinfunction "AY2_40") (pintype "bidirectional"))
      (node (ref "U10") (pin "42") (pinfunction "AX3_42") (pintype "bidirectional"))
      (node (ref "U10") (pin "43") (pinfunction "AX0_43") (pintype "bidirectional"))
      (node (ref "U11") (pin "10") (pinfunction "P_/__S_10") (pintype "bidirectional"))
      (node (ref "U11") (pin "12") (pinfunction "GND_12") (pintype "power_in"))
      (node (ref "U11") (pin "18") (pinfunction "AX1_18") (pintype "bidirectional"))
      (node (ref "U11") (pin "19") (pinfunction "AX2_19") (pintype "bidirectional"))
      (node (ref "U11") (pin "20") (pinfunction "AY0_20") (pintype "bidirectional"))
      (node (ref "U11") (pin "21") (pinfunction "AY1_21") (pintype "bidirectional"))
      (node (ref "U11") (pin "40") (pinfunction "AY2_40") (pintype "bidirectional"))
      (node (ref "U11") (pin "42") (pinfunction "AX3_42") (pintype "bidirectional"))
      (node (ref "U11") (pin "43") (pinfunction "AX0_43") (pintype "bidirectional"))
      (node (ref "U12") (pin "10") (pinfunction "P_/__S_10") (pintype "bidirectional"))
      (node (ref "U12") (pin "12") (pinfunction "GND_12") (pintype "power_in"))
      (node (ref "U12") (pin "18") (pinfunction "AX1_18") (pintype "bidirectional"))
      (node (ref "U12") (pin "19") (pinfunction "AX2_19") (pintype "bidirectional"))
      (node (ref "U12") (pin "20") (pinfunction "AY0_20") (pintype "bidirectional"))
      (node (ref "U12") (pin "21") (pinfunction "AY1_21") (pintype "bidirectional"))
      (node (ref "U12") (pin "40") (pinfunction "AY2_40") (pintype "bidirectional"))
      (node (ref "U12") (pin "42") (pinfunction "AX3_42") (pintype "bidirectional"))
      (node (ref "U12") (pin "43") (pinfunction "AX0_43") (pintype "bidirectional"))
      (node (ref "U5") (pin "10") (pinfunction "P_/__S_10") (pintype "bidirectional"))
      (node (ref "U5") (pin "12") (pinfunction "GND_12") (pintype "power_in"))
      (node (ref "U5") (pin "18") (pinfunction "AX1_18") (pintype "bidirectional"))
      (node (ref "U5") (pin "19") (pinfunction "AX2_19") (pintype "bidirectional"))
      (node (ref "U5") (pin "20") (pinfunction "AY0_20") (pintype "bidirectional"))
      (node (ref "U5") (pin "21") (pinfunction "AY1_21") (pintype "bidirectional"))
      (node (ref "U5") (pin "40") (pinfunction "AY2_40") (pintype "bidirectional"))
      (node (ref "U5") (pin "42") (pinfunction "AX3_42") (pintype "bidirectional"))
      (node (ref "U5") (pin "43") (pinfunction "AX0_43") (pintype "bidirectional"))
      (node (ref "U6") (pin "10") (pinfunction "P_/__S_10") (pintype "bidirectional"))
      (node (ref "U6") (pin "12") (pinfunction "GND_12") (pintype "power_in"))
      (node (ref "U6") (pin "18") (pinfunction "AX1_18") (pintype "bidirectional"))
      (node (ref "U6") (pin "19") (pinfunction "AX2_19") (pintype "bidirectional"))
      (node (ref "U6") (pin "20") (pinfunction "AY0_20") (pintype "bidirectional"))
      (node (ref "U6") (pin "21") (pinfunction "AY1_21") (pintype "bidirectional"))
      (node (ref "U6") (pin "40") (pinfunction "AY2_40") (pintype "bidirectional"))
      (node (ref "U6") (pin "42") (pinfunction "AX3_42") (pintype "bidirectional"))
      (node (ref "U6") (pin "43") (pinfunction "AX0_43") (pintype "bidirectional"))
      (node (ref "U7") (pin "10") (pinfunction "P_/__S_10") (pintype "bidirectional"))
      (node (ref "U7") (pin "12") (pinfunction "GND_12") (pintype "power_in"))
      (node (ref "U7") (pin "18") (pinfunction "AX1_18") (pintype "bidirectional"))
      (node (ref "U7") (pin "19") (pinfunction "AX2_19") (pintype "bidirectional"))
      (node (ref "U7") (pin "20") (pinfunction "AY0_20") (pintype "bidirectional"))
      (node (ref "U7") (pin "21") (pinfunction "AY1_21") (pintype "bidirectional"))
      (node (ref "U7") (pin "40") (pinfunction "AY2_40") (pintype "bidirectional"))
      (node (ref "U7") (pin "42") (pinfunction "AX3_42") (pintype "bidirectional"))
      (node (ref "U7") (pin "43") (pinfunction "AX0_43") (pintype "bidirectional"))
      (node (ref "U8") (pin "10") (pinfunction "P_/__S_10") (pintype "bidirectional"))
      (node (ref "U8") (pin "12") (pinfunction "GND_12") (pintype "power_in"))
      (node (ref "U8") (pin "18") (pinfunction "AX1_18") (pintype "bidirectional"))
      (node (ref "U8") (pin "19") (pinfunction "AX2_19") (pintype "bidirectional"))
      (node (ref "U8") (pin "20") (pinfunction "AY0_20") (pintype "bidirectional"))
      (node (ref "U8") (pin "21") (pinfunction "AY1_21") (pintype "bidirectional"))
      (node (ref "U8") (pin "40") (pinfunction "AY2_40") (pintype "bidirectional"))
      (node (ref "U8") (pin "42") (pinfunction "AX3_42") (pintype "bidirectional"))
      (node (ref "U8") (pin "43") (pinfunction "AX0_43") (pintype "bidirectional"))
      (node (ref "U9") (pin "10") (pinfunction "P_/__S_10") (pintype "bidirectional"))
      (node (ref "U9") (pin "12") (pinfunction "GND_12") (pintype "power_in"))
      (node (ref "U9") (pin "18") (pinfunction "AX1_18") (pintype "bidirectional"))
      (node (ref "U9") (pin "19") (pinfunction "AX2_19") (pintype "bidirectional"))
      (node (ref "U9") (pin "20") (pinfunction "AY0_20") (pintype "bidirectional"))
      (node (ref "U9") (pin "21") (pinfunction "AY1_21") (pintype "bidirectional"))
      (node (ref "U9") (pin "40") (pinfunction "AY2_40") (pintype "bidirectional"))
      (node (ref "U9") (pin "42") (pinfunction "AX3_42") (pintype "bidirectional"))
      (node (ref "U9") (pin "43") (pinfunction "AX0_43") (pintype "bidirectional"))
    )
    (net (code "171") (name "unconnected-(U5-NC-Pad9)") (class "Default")
      (node (ref "U5") (pin "9") (pinfunction "NC_9") (pintype "input+no_connect"))
    )
    (net (code "172") (name "unconnected-(U5-NC-Pad22)") (class "Default")
      (node (ref "U5") (pin "22") (pinfunction "NC_22") (pintype "input+no_connect"))
    )
    (net (code "173") (name "unconnected-(U5-NC-Pad23)") (class "Default")
      (node (ref "U5") (pin "23") (pinfunction "NC_23") (pintype "input+no_connect"))
    )
    (net (code "174") (name "unconnected-(U5-NC-Pad32)") (class "Default")
      (node (ref "U5") (pin "32") (pinfunction "NC_32") (pintype "input+no_connect"))
    )
    (net (code "175") (name "unconnected-(U5-NC-Pad44)") (class "Default")
      (node (ref "U5") (pin "44") (pinfunction "NC_44") (pintype "input+no_connect"))
    )
    (net (code "176") (name "unconnected-(U6-NC-Pad9)") (class "Default")
      (node (ref "U6") (pin "9") (pinfunction "NC_9") (pintype "input+no_connect"))
    )
    (net (code "177") (name "unconnected-(U6-NC-Pad22)") (class "Default")
      (node (ref "U6") (pin "22") (pinfunction "NC_22") (pintype "input+no_connect"))
    )
    (net (code "178") (name "unconnected-(U6-NC-Pad23)") (class "Default")
      (node (ref "U6") (pin "23") (pinfunction "NC_23") (pintype "input+no_connect"))
    )
    (net (code "179") (name "unconnected-(U6-NC-Pad32)") (class "Default")
      (node (ref "U6") (pin "32") (pinfunction "NC_32") (pintype "input+no_connect"))
    )
    (net (code "180") (name "unconnected-(U6-NC-Pad44)") (class "Default")
      (node (ref "U6") (pin "44") (pinfunction "NC_44") (pintype "input+no_connect"))
    )
    (net (code "181") (name "unconnected-(U7-NC-Pad9)") (class "Default")
      (node (ref "U7") (pin "9") (pinfunction "NC_9") (pintype "input+no_connect"))
    )
    (net (code "182") (name "unconnected-(U7-NC-Pad22)") (class "Default")
      (node (ref "U7") (pin "22") (pinfunction "NC_22") (pintype "input+no_connect"))
    )
    (net (code "183") (name "unconnected-(U7-NC-Pad23)") (class "Default")
      (node (ref "U7") (pin "23") (pinfunction "NC_23") (pintype "input+no_connect"))
    )
    (net (code "184") (name "unconnected-(U7-NC-Pad32)") (class "Default")
      (node (ref "U7") (pin "32") (pinfunction "NC_32") (pintype "input+no_connect"))
    )
    (net (code "185") (name "unconnected-(U7-NC-Pad44)") (class "Default")
      (node (ref "U7") (pin "44") (pinfunction "NC_44") (pintype "input+no_connect"))
    )
    (net (code "186") (name "unconnected-(U8-NC-Pad9)") (class "Default")
      (node (ref "U8") (pin "9") (pinfunction "NC_9") (pintype "input+no_connect"))
    )
    (net (code "187") (name "unconnected-(U8-NC-Pad22)") (class "Default")
      (node (ref "U8") (pin "22") (pinfunction "NC_22") (pintype "input+no_connect"))
    )
    (net (code "188") (name "unconnected-(U8-NC-Pad23)") (class "Default")
      (node (ref "U8") (pin "23") (pinfunction "NC_23") (pintype "input+no_connect"))
    )
    (net (code "189") (name "unconnected-(U8-NC-Pad32)") (class "Default")
      (node (ref "U8") (pin "32") (pinfunction "NC_32") (pintype "input+no_connect"))
    )
    (net (code "190") (name "unconnected-(U8-NC-Pad44)") (class "Default")
      (node (ref "U8") (pin "44") (pinfunction "NC_44") (pintype "input+no_connect"))
    )
    (net (code "191") (name "unconnected-(U9-NC-Pad9)") (class "Default")
      (node (ref "U9") (pin "9") (pinfunction "NC_9") (pintype "input+no_connect"))
    )
    (net (code "192") (name "unconnected-(U9-NC-Pad22)") (class "Default")
      (node (ref "U9") (pin "22") (pinfunction "NC_22") (pintype "input+no_connect"))
    )
    (net (code "193") (name "unconnected-(U9-NC-Pad23)") (class "Default")
      (node (ref "U9") (pin "23") (pinfunction "NC_23") (pintype "input+no_connect"))
    )
    (net (code "194") (name "unconnected-(U9-NC-Pad32)") (class "Default")
      (node (ref "U9") (pin "32") (pinfunction "NC_32") (pintype "input+no_connect"))
    )
    (net (code "195") (name "unconnected-(U9-NC-Pad44)") (class "Default")
      (node (ref "U9") (pin "44") (pinfunction "NC_44") (pintype "input+no_connect"))
    )
    (net (code "196") (name "unconnected-(U10-NC-Pad9)") (class "Default")
      (node (ref "U10") (pin "9") (pinfunction "NC_9") (pintype "input+no_connect"))
    )
    (net (code "197") (name "unconnected-(U10-NC-Pad22)") (class "Default")
      (node (ref "U10") (pin "22") (pinfunction "NC_22") (pintype "input+no_connect"))
    )
    (net (code "198") (name "unconnected-(U10-NC-Pad23)") (class "Default")
      (node (ref "U10") (pin "23") (pinfunction "NC_23") (pintype "input+no_connect"))
    )
    (net (code "199") (name "unconnected-(U10-NC-Pad32)") (class "Default")
      (node (ref "U10") (pin "32") (pinfunction "NC_32") (pintype "input+no_connect"))
    )
    (net (code "200") (name "unconnected-(U10-NC-Pad44)") (class "Default")
      (node (ref "U10") (pin "44") (pinfunction "NC_44") (pintype "input+no_connect"))
    )
    (net (code "201") (name "unconnected-(U11-NC-Pad9)") (class "Default")
      (node (ref "U11") (pin "9") (pinfunction "NC_9") (pintype "input+no_connect"))
    )
    (net (code "202") (name "unconnected-(U11-NC-Pad22)") (class "Default")
      (node (ref "U11") (pin "22") (pinfunction "NC_22") (pintype "input+no_connect"))
    )
    (net (code "203") (name "unconnected-(U11-NC-Pad23)") (class "Default")
      (node (ref "U11") (pin "23") (pinfunction "NC_23") (pintype "input+no_connect"))
    )
    (net (code "204") (name "unconnected-(U11-NC-Pad32)") (class "Default")
      (node (ref "U11") (pin "32") (pinfunction "NC_32") (pintype "input+no_connect"))
    )
    (net (code "205") (name "unconnected-(U11-NC-Pad44)") (class "Default")
      (node (ref "U11") (pin "44") (pinfunction "NC_44") (pintype "input+no_connect"))
    )
    (net (code "206") (name "unconnected-(U12-NC-Pad9)") (class "Default")
      (node (ref "U12") (pin "9") (pinfunction "NC_9") (pintype "input+no_connect"))
    )
    (net (code "207") (name "unconnected-(U12-NC-Pad22)") (class "Default")
      (node (ref "U12") (pin "22") (pinfunction "NC_22") (pintype "input+no_connect"))
    )
    (net (code "208") (name "unconnected-(U12-NC-Pad23)") (class "Default")
      (node (ref "U12") (pin "23") (pinfunction "NC_23") (pintype "input+no_connect"))
    )
    (net (code "209") (name "unconnected-(U12-NC-Pad32)") (class "Default")
      (node (ref "U12") (pin "32") (pinfunction "NC_32") (pintype "input+no_connect"))
    )
    (net (code "210") (name "unconnected-(U12-NC-Pad44)") (class "Default")
      (node (ref "U12") (pin "44") (pinfunction "NC_44") (pintype "input+no_connect"))
    )
  )
)
